# hometrainer.net
KiCad netlist of a schematic drawn in Altium Designer
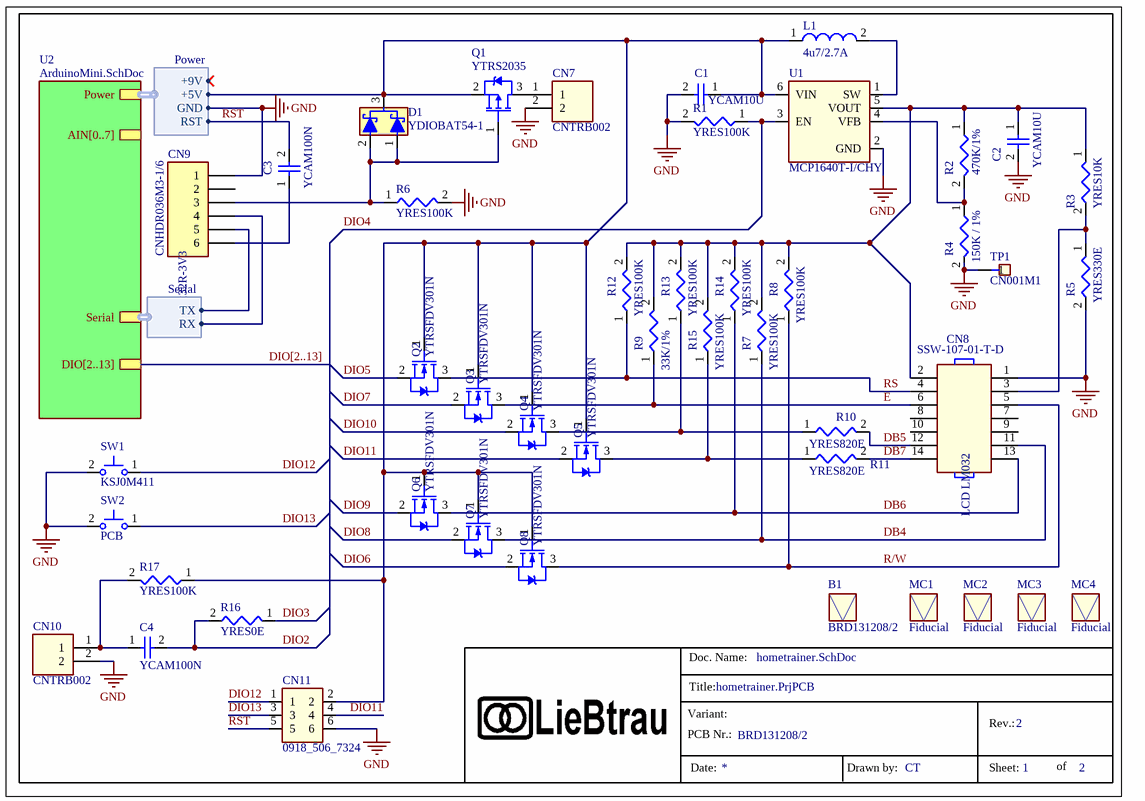
[diagram p0: hometrainer.SchDoc]

(export (version "E")
  (design (tool "Eeschema 10.0.6"))
  (components
    (comp (ref "B1")
      (value "~")
      (footprint "MC_BoardNr")
      (fields (field (name "PART NUMBER") "BARE_PCB"))
      (libsource (lib "Testing") (part "BD_PCB"))
    )
    (comp (ref "C1") (value "YCAM10U") (footprint "CA_1206") (libsource (lib "Testing") (part "CA_NONPOL")))
    (comp (ref "C2") (value "YCAM10U") (footprint "CA_1206") (libsource (lib "Testing") (part "CA_NONPOL")))
    (comp (ref "C3") (value "YCAM100N") (footprint "CA_1206") (libsource (lib "Testing") (part "CA_NONPOL")))
    (comp (ref "C4") (value "YCAM100N") (footprint "CA_1206") (libsource (lib "Testing") (part "CA_NONPOL")))
    (comp (ref "CN7")
      (value "CNTRB002")
      (footprint "CN_MKDSN 1,5/2")
      (libsource (lib "Testing") (part "CN_2P"))
    )
    (comp (ref "CN8")
      (value "SSW-107-01-T-D")
      (footprint "CN_SCKT2X7")
      (fields (field (name "MANUFACTURER") "Samtec"))
      (libsource (lib "Testing") (part "CN_2x7P"))
    )
    (comp (ref "CN9")
      (value "CNHDR036M3-1/6")
      (footprint "CN_HDR1X6")
      (libsource (lib "Testing") (part "CN_6P"))
    )
    (comp (ref "CN10") (value "CNTRB002") (footprint "CN_MKDSN 1,5/2") (libsource (lib "") (part "CN_2P_1")))
    (comp (ref "CN11")
      (value "0918_506_7324")
      (footprint "CN_HARTING_918506X324")
      (fields (field (name "MANUFACTURER") "Harting"))
      (libsource (lib "Testing") (part "CN_2x3P"))
    )
    (comp (ref "D1")
      (value "YDIOBAT54-1")
      (footprint "SC_SOT23")
      (description "Dual Schottky Barrier Diode Common Cathode")
      (fields (field (name "MANUFACTURER") "Fairchild Semiconductor"))
      (libsource (lib "Testing") (part "DI_SCHOTTKY_2_CC"))
    )
    (comp (ref "L1")
      (value "4u7/2.7A")
      (footprint "CL_STD_2220")
      (fields (field (name "PART NUMBER") "LQH55DN4R7M03L") (field (name "MANUFACTURER") "Murata"))
      (libsource (lib "Testing") (part "CL_COIL"))
    )
    (comp (ref "MC1")
      (value "Fiducial")
      (footprint "MC_FIDUCIAL")
      (libsource (lib "Testing") (part "MC_MechPart_No_BOM"))
    )
    (comp (ref "MC2")
      (value "Fiducial")
      (footprint "MC_FIDUCIAL")
      (libsource (lib "Testing") (part "MC_MechPart_No_BOM"))
    )
    (comp (ref "MC3")
      (value "Fiducial")
      (footprint "MC_FIDUCIAL")
      (libsource (lib "Testing") (part "MC_MechPart_No_BOM"))
    )
    (comp (ref "MC4")
      (value "Fiducial")
      (footprint "MC_FIDUCIAL")
      (libsource (lib "Testing") (part "MC_MechPart_No_BOM"))
    )
    (comp (ref "Q1")
      (value "YTRS2035")
      (footprint "SC_SOT23")
      (fields (field (name "MANUFACTURER") "Diodes Inc."))
      (libsource (lib "Testing") (part "TR_PMOS"))
    )
    (comp (ref "Q2")
      (value "YTRSFDV301N")
      (footprint "SC_SOT23")
      (fields (field (name "MANUFACTURER") "FAIRCHILD SEMICONDUCTOR"))
      (libsource (lib "Testing") (part "TR_NMOS"))
    )
    (comp (ref "Q3")
      (value "YTRSFDV301N")
      (footprint "SC_SOT23")
      (fields (field (name "MANUFACTURER") "FAIRCHILD SEMICONDUCTOR"))
      (libsource (lib "Testing") (part "TR_NMOS"))
    )
    (comp (ref "Q4")
      (value "YTRSFDV301N")
      (footprint "SC_SOT23")
      (fields (field (name "MANUFACTURER") "FAIRCHILD SEMICONDUCTOR"))
      (libsource (lib "Testing") (part "TR_NMOS"))
    )
    (comp (ref "Q5")
      (value "YTRSFDV301N")
      (footprint "SC_SOT23")
      (fields (field (name "MANUFACTURER") "FAIRCHILD SEMICONDUCTOR"))
      (libsource (lib "Testing") (part "TR_NMOS"))
    )
    (comp (ref "Q6")
      (value "YTRSFDV301N")
      (footprint "SC_SOT23")
      (fields (field (name "MANUFACTURER") "FAIRCHILD SEMICONDUCTOR"))
      (libsource (lib "Testing") (part "TR_NMOS"))
    )
    (comp (ref "Q7")
      (value "YTRSFDV301N")
      (footprint "SC_SOT23")
      (fields (field (name "MANUFACTURER") "FAIRCHILD SEMICONDUCTOR"))
      (libsource (lib "Testing") (part "TR_NMOS"))
    )
    (comp (ref "Q8")
      (value "YTRSFDV301N")
      (footprint "SC_SOT23")
      (fields (field (name "MANUFACTURER") "FAIRCHILD SEMICONDUCTOR"))
      (libsource (lib "Testing") (part "TR_NMOS"))
    )
    (comp (ref "R1")
      (value "YRES100K")
      (footprint "RE_1206")
      (description "Resistor")
      (fields (field (name "MANUFACTURER") "Multicomp"))
      (libsource (lib "Testing") (part "RE_RES"))
    )
    (comp (ref "R2")
      (value "470K/1%")
      (footprint "RE_1206")
      (description "Resistor")
      (fields (field (name "PART NUMBER") "CRCW1206470KFKEA") (field (name "MANUFACTURER") "Vishay Draloric"))
      (libsource (lib "Testing") (part "RE_RES"))
    )
    (comp (ref "R3")
      (value "YRES10K")
      (footprint "RE_1206")
      (description "Resistor")
      (fields (field (name "MANUFACTURER") "Vishay Draloric"))
      (libsource (lib "Testing") (part "RE_RES"))
    )
    (comp (ref "R4")
      (value "150K / 1%")
      (footprint "RE_1206")
      (description "Resistor")
      (fields (field (name "PART NUMBER") "RC1206FR-07150KL") (field (name "MANUFACTURER") "Yageo (Phycomp)"))
      (libsource (lib "Testing") (part "RE_RES"))
    )
    (comp (ref "R5")
      (value "YRES330E")
      (footprint "RE_1206")
      (description "Resistor")
      (fields (field (name "MANUFACTURER") "Welwyn"))
      (libsource (lib "Testing") (part "RE_RES"))
    )
    (comp (ref "R6")
      (value "YRES100K")
      (footprint "RE_1206")
      (description "Resistor")
      (fields (field (name "MANUFACTURER") "Multicomp"))
      (libsource (lib "Testing") (part "RE_RES"))
    )
    (comp (ref "R7")
      (value "YRES100K")
      (footprint "RE_1206")
      (description "Resistor")
      (fields (field (name "MANUFACTURER") "Multicomp"))
      (libsource (lib "Testing") (part "RE_RES"))
    )
    (comp (ref "R8")
      (value "YRES100K")
      (footprint "RE_1206")
      (description "Resistor")
      (fields (field (name "MANUFACTURER") "Multicomp"))
      (libsource (lib "Testing") (part "RE_RES"))
    )
    (comp (ref "R9")
      (value "33K/1%")
      (footprint "RE_1206")
      (description "Resistor")
      (fields (field (name "PART NUMBER") "MCMR12X3302FTL") (field (name "MANUFACTURER") "Multicomp"))
      (libsource (lib "Testing") (part "RE_RES"))
    )
    (comp (ref "R10")
      (value "YRES820E")
      (footprint "RE_1206")
      (description "Resistor")
      (libsource (lib "Testing") (part "RE_RES"))
    )
    (comp (ref "R11")
      (value "YRES820E")
      (footprint "RE_1206")
      (description "Resistor")
      (libsource (lib "Testing") (part "RE_RES"))
    )
    (comp (ref "R12")
      (value "YRES100K")
      (footprint "RE_1206")
      (description "Resistor")
      (fields (field (name "MANUFACTURER") "Multicomp"))
      (libsource (lib "Testing") (part "RE_RES"))
    )
    (comp (ref "R13")
      (value "YRES100K")
      (footprint "RE_1206")
      (description "Resistor")
      (fields (field (name "MANUFACTURER") "Multicomp"))
      (libsource (lib "Testing") (part "RE_RES"))
    )
    (comp (ref "R14")
      (value "YRES100K")
      (footprint "RE_1206")
      (description "Resistor")
      (fields (field (name "MANUFACTURER") "Multicomp"))
      (libsource (lib "Testing") (part "RE_RES"))
    )
    (comp (ref "R15")
      (value "YRES100K")
      (footprint "RE_1206")
      (description "Resistor")
      (fields (field (name "MANUFACTURER") "Multicomp"))
      (libsource (lib "Testing") (part "RE_RES"))
    )
    (comp (ref "R16")
      (value "YRES0E")
      (footprint "RE_1206")
      (description "Resistor")
      (fields (field (name "MANUFACTURER") "Vishay Draloric"))
      (libsource (lib "Testing") (part "RE_RES"))
    )
    (comp (ref "R17")
      (value "YRES100K")
      (footprint "RE_1206")
      (description "Resistor")
      (fields (field (name "MANUFACTURER") "Multicomp"))
      (libsource (lib "Testing") (part "RE_RES"))
    )
    (comp (ref "SW1")
      (value "KSJ0M411")
      (footprint "SW_KSJ-M")
      (fields (field (name "MANUFACTURER") "C&K"))
      (libsource (lib "Testing") (part "SW_SPST"))
    )
    (comp (ref "SW2")
      (value "PCB")
      (footprint "SW_PCB")
      (fields (field (name "PART NUMBER") "PCB_SWITCH"))
      (libsource (lib "Testing") (part "SW_SPST"))
    )
    (comp (ref "TP1")
      (value "CN001M1")
      (footprint "CN_TP_TH_1.3mm")
      (libsource (lib "Testing") (part "CN_TESTPIN"))
    )
    (comp (ref "U1")
      (value "MCP1640T-I/CHY")
      (footprint "SC_SOT23-6")
      (fields (field (name "MANUFACTURER") "Microchip"))
      (libsource (lib "Testing") (part "IC_MCP1640"))
    )
  )
  (nets
    (net (code "3") (name "/+5V") (class "Default")
      (node (ref "C1") (pin "1") (pinfunction "1_1") (pintype "passive"))
      (node (ref "CN11") (pin "2") (pinfunction "2_2") (pintype "passive"))
      (node (ref "D1") (pin "3") (pinfunction "C_3") (pintype "passive"))
      (node (ref "L1") (pin "1") (pinfunction "1_1") (pintype "passive"))
      (node (ref "Q1") (pin "2") (pinfunction "S_2") (pintype "passive"))
      (node (ref "Q2") (pin "1") (pinfunction "G_1") (pintype "passive"))
      (node (ref "Q3") (pin "1") (pinfunction "G_1") (pintype "passive"))
      (node (ref "Q4") (pin "1") (pinfunction "G_1") (pintype "passive"))
      (node (ref "Q5") (pin "1") (pinfunction "G_1") (pintype "passive"))
      (node (ref "Q6") (pin "1") (pinfunction "G_1") (pintype "passive"))
      (node (ref "Q7") (pin "1") (pinfunction "G_1") (pintype "passive"))
      (node (ref "Q8") (pin "1") (pinfunction "G_1") (pintype "passive"))
      (node (ref "R17") (pin "1") (pinfunction "1_1") (pintype "passive"))
      (node (ref "U1") (pin "6") (pinfunction "VIN_6") (pintype "passive"))
    )
    (net (code "5") (name "/DB4") (class "Default")
      (node (ref "CN8") (pin "11") (pinfunction "11_11") (pintype "passive"))
      (node (ref "Q7") (pin "3") (pinfunction "D_3") (pintype "passive"))
      (node (ref "R7") (pin "1") (pinfunction "1_1") (pintype "passive"))
    )
    (net (code "6") (name "/DB5") (class "Default")
      (node (ref "CN8") (pin "12") (pinfunction "12_12") (pintype "passive"))
      (node (ref "R10") (pin "2") (pinfunction "2_2") (pintype "passive"))
    )
    (net (code "7") (name "/DB6") (class "Default")
      (node (ref "CN8") (pin "13") (pinfunction "13_13") (pintype "passive"))
      (node (ref "Q6") (pin "3") (pinfunction "D_3") (pintype "passive"))
      (node (ref "R14") (pin "1") (pinfunction "1_1") (pintype "passive"))
    )
    (net (code "8") (name "/DB7") (class "Default")
      (node (ref "CN8") (pin "14") (pinfunction "14_14") (pintype "passive"))
      (node (ref "R11") (pin "2") (pinfunction "2_2") (pintype "passive"))
    )
    (net (code "9") (name "/DIO2") (class "Default")
      (node (ref "C4") (pin "2") (pinfunction "2_2") (pintype "passive"))
      (node (ref "R16") (pin "2") (pinfunction "2_2") (pintype "passive"))
    )
    (net (code "10") (name "/DIO3") (class "Default")
      (node (ref "R16") (pin "1") (pinfunction "1_1") (pintype "passive"))
    )
    (net (code "11") (name "/DIO4") (class "Default")
      (node (ref "R1") (pin "1") (pinfunction "1_1") (pintype "passive"))
      (node (ref "U1") (pin "3") (pinfunction "EN_3") (pintype "passive"))
    )
    (net (code "12") (name "/DIO5") (class "Default")
      (node (ref "Q2") (pin "2") (pinfunction "S_2") (pintype "passive"))
    )
    (net (code "13") (name "/DIO6") (class "Default")
      (node (ref "Q8") (pin "2") (pinfunction "S_2") (pintype "passive"))
    )
    (net (code "14") (name "/DIO7") (class "Default")
      (node (ref "Q3") (pin "2") (pinfunction "S_2") (pintype "passive"))
    )
    (net (code "15") (name "/DIO8") (class "Default")
      (node (ref "Q7") (pin "2") (pinfunction "S_2") (pintype "passive"))
    )
    (net (code "16") (name "/DIO9") (class "Default")
      (node (ref "Q6") (pin "2") (pinfunction "S_2") (pintype "passive"))
    )
    (net (code "17") (name "/DIO10") (class "Default")
      (node (ref "Q4") (pin "2") (pinfunction "S_2") (pintype "passive"))
    )
    (net (code "18") (name "/DIO11") (class "Default")
      (node (ref "CN11") (pin "4") (pinfunction "4_4") (pintype "passive"))
      (node (ref "Q5") (pin "2") (pinfunction "S_2") (pintype "passive"))
    )
    (net (code "19") (name "/DIO12") (class "Default")
      (node (ref "CN11") (pin "1") (pinfunction "1_1") (pintype "passive"))
      (node (ref "SW1") (pin "1") (pinfunction "1_1") (pintype "passive"))
    )
    (net (code "20") (name "/DIO13") (class "Default")
      (node (ref "CN11") (pin "3") (pinfunction "3_3") (pintype "passive"))
      (node (ref "SW2") (pin "1") (pinfunction "1_1") (pintype "passive"))
    )
    (net (code "22") (name "/E") (class "Default")
      (node (ref "CN8") (pin "6") (pinfunction "6_6") (pintype "passive"))
      (node (ref "Q3") (pin "3") (pinfunction "D_3") (pintype "passive"))
      (node (ref "R9") (pin "1") (pinfunction "1_1") (pintype "passive"))
    )
    (net (code "23") (name "/RS") (class "Default")
      (node (ref "CN8") (pin "4") (pinfunction "4_4") (pintype "passive"))
      (node (ref "Q2") (pin "3") (pinfunction "D_3") (pintype "passive"))
      (node (ref "R12") (pin "1") (pinfunction "1_1") (pintype "passive"))
    )
    (net (code "24") (name "/RST") (class "Default")
      (node (ref "C3") (pin "2") (pinfunction "2_2") (pintype "passive"))
      (node (ref "CN11") (pin "5") (pinfunction "5_5") (pintype "passive"))
    )
    (net (code "25") (name "/RX") (class "Default")
      (node (ref "CN9") (pin "4") (pinfunction "4_4") (pintype "passive"))
    )
    (net (code "26") (name "/R{slash}W") (class "Default")
      (node (ref "CN8") (pin "5") (pinfunction "5_5") (pintype "passive"))
      (node (ref "Q8") (pin "3") (pinfunction "D_3") (pintype "passive"))
      (node (ref "R8") (pin "1") (pinfunction "1_1") (pintype "passive"))
    )
    (net (code "27") (name "/TX") (class "Default")
      (node (ref "CN9") (pin "5") (pinfunction "5_5") (pintype "passive"))
    )
    (net (code "30") (name "GND") (class "Default")
      (node (ref "C1") (pin "2") (pinfunction "2_2") (pintype "passive"))
      (node (ref "C2") (pin "2") (pinfunction "2_2") (pintype "passive"))
      (node (ref "CN10") (pin "2") (pinfunction "2_2") (pintype "passive"))
      (node (ref "CN11") (pin "6") (pinfunction "6_6") (pintype "passive"))
      (node (ref "CN7") (pin "2") (pinfunction "2_2") (pintype "passive"))
      (node (ref "CN8") (pin "1") (pinfunction "1_1") (pintype "passive"))
      (node (ref "CN9") (pin "1") (pinfunction "1_1") (pintype "passive"))
      (node (ref "R1") (pin "2") (pinfunction "2_2") (pintype "passive"))
      (node (ref "R4") (pin "2") (pinfunction "2_2") (pintype "passive"))
      (node (ref "R5") (pin "2") (pinfunction "2_2") (pintype "passive"))
      (node (ref "R6") (pin "2") (pinfunction "2_2") (pintype "passive"))
      (node (ref "SW1") (pin "2") (pinfunction "2_2") (pintype "passive"))
      (node (ref "SW2") (pin "2") (pinfunction "2_2") (pintype "passive"))
      (node (ref "TP1") (pin "1") (pinfunction "1_1") (pintype "passive"))
      (node (ref "U1") (pin "2") (pinfunction "GND_2") (pintype "passive"))
    )
    (net (code "31") (name "Net-(C3-Pad1)") (class "Default")
      (node (ref "C3") (pin "1") (pinfunction "1_1") (pintype "passive"))
      (node (ref "CN9") (pin "6") (pinfunction "6_6") (pintype "passive"))
    )
    (net (code "32") (name "Net-(C4-Pad1)") (class "Default")
      (node (ref "C4") (pin "1") (pinfunction "1_1") (pintype "passive"))
      (node (ref "CN10") (pin "1") (pinfunction "1_1") (pintype "passive"))
      (node (ref "R17") (pin "2") (pinfunction "2_2") (pintype "passive"))
    )
    (net (code "33") (name "Net-(CN8-Pad3)") (class "Default")
      (node (ref "CN8") (pin "3") (pinfunction "3_3") (pintype "passive"))
      (node (ref "R3") (pin "2") (pinfunction "2_2") (pintype "passive"))
      (node (ref "R5") (pin "1") (pinfunction "1_1") (pintype "passive"))
    )
    (net (code "34") (name "Net-(D1-A1)") (class "Default")
      (node (ref "CN9") (pin "3") (pinfunction "3_3") (pintype "passive"))
      (node (ref "D1") (pin "1") (pinfunction "A1_1") (pintype "passive"))
      (node (ref "D1") (pin "2") (pinfunction "A2_2") (pintype "passive"))
      (node (ref "Q1") (pin "1") (pinfunction "G_1") (pintype "passive"))
      (node (ref "R6") (pin "1") (pinfunction "1_1") (pintype "passive"))
    )
    (net (code "35") (name "Net-(Q1-D)") (class "Default")
      (node (ref "CN7") (pin "1") (pinfunction "1_1") (pintype "passive"))
      (node (ref "Q1") (pin "3") (pinfunction "D_3") (pintype "passive"))
    )
    (net (code "36") (name "Net-(Q4-D)") (class "Default")
      (node (ref "Q4") (pin "3") (pinfunction "D_3") (pintype "passive"))
      (node (ref "R10") (pin "1") (pinfunction "1_1") (pintype "passive"))
      (node (ref "R13") (pin "1") (pinfunction "1_1") (pintype "passive"))
    )
    (net (code "37") (name "Net-(Q5-D)") (class "Default")
      (node (ref "Q5") (pin "3") (pinfunction "D_3") (pintype "passive"))
      (node (ref "R11") (pin "1") (pinfunction "1_1") (pintype "passive"))
      (node (ref "R15") (pin "1") (pinfunction "1_1") (pintype "passive"))
    )
    (net (code "38") (name "Net-(U1-SW)") (class "Default")
      (node (ref "L1") (pin "2") (pinfunction "2_2") (pintype "passive"))
      (node (ref "U1") (pin "1") (pinfunction "SW_1") (pintype "passive"))
    )
    (net (code "39") (name "Net-(U1-VFB)") (class "Default")
      (node (ref "R2") (pin "2") (pinfunction "2_2") (pintype "passive"))
      (node (ref "R4") (pin "1") (pinfunction "1_1") (pintype "passive"))
      (node (ref "U1") (pin "4") (pinfunction "VFB_4") (pintype "passive"))
    )
    (net (code "40") (name "Net-(U1-VOUT)") (class "Default")
      (node (ref "C2") (pin "1") (pinfunction "1_1") (pintype "passive"))
      (node (ref "CN8") (pin "2") (pinfunction "2_2") (pintype "passive"))
      (node (ref "R12") (pin "2") (pinfunction "2_2") (pintype "passive"))
      (node (ref "R13") (pin "2") (pinfunction "2_2") (pintype "passive"))
      (node (ref "R14") (pin "2") (pinfunction "2_2") (pintype "passive"))
      (node (ref "R15") (pin "2") (pinfunction "2_2") (pintype "passive"))
      (node (ref "R2") (pin "1") (pinfunction "1_1") (pintype "passive"))
      (node (ref "R3") (pin "1") (pinfunction "1_1") (pintype "passive"))
      (node (ref "R7") (pin "2") (pinfunction "2_2") (pintype "passive"))
      (node (ref "R8") (pin "2") (pinfunction "2_2") (pintype "passive"))
      (node (ref "R9") (pin "2") (pinfunction "2_2") (pintype "passive"))
      (node (ref "U1") (pin "5") (pinfunction "VOUT_5") (pintype "passive"))
    )
    (net (code "41") (name "unconnected-(CN8-Pad7)") (class "Default")
      (node (ref "CN8") (pin "7") (pinfunction "7_7") (pintype "passive"))
    )
    (net (code "42") (name "unconnected-(CN8-Pad8)") (class "Default")
      (node (ref "CN8") (pin "8") (pinfunction "8_8") (pintype "passive"))
    )
    (net (code "43") (name "unconnected-(CN8-Pad9)") (class "Default")
      (node (ref "CN8") (pin "9") (pinfunction "9_9") (pintype "passive"))
    )
    (net (code "44") (name "unconnected-(CN8-Pad10)") (class "Default")
      (node (ref "CN8") (pin "10") (pinfunction "10_10") (pintype "passive"))
    )
    (net (code "45") (name "unconnected-(CN9-Pad2)") (class "Default")
      (node (ref "CN9") (pin "2") (pinfunction "2_2") (pintype "passive"))
    )
  )
)
